# 7474-strobe-generator-v2.net
KiCad netlist of a schematic drawn in EAGLE
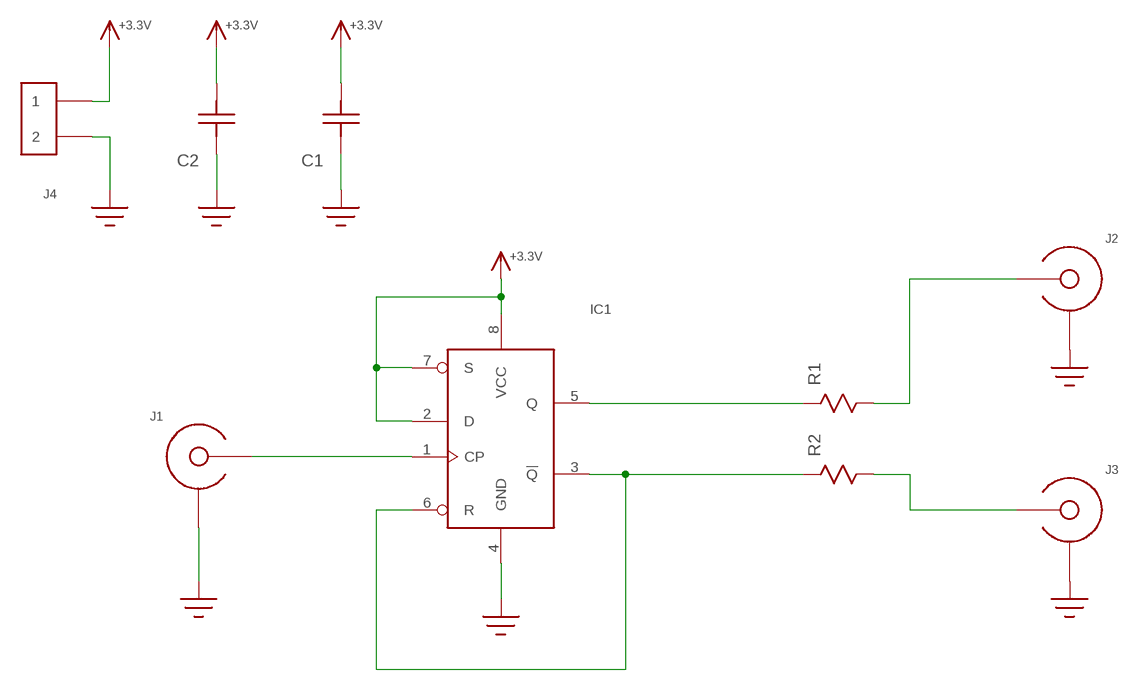
[diagram p0: schematic, sheet 1]

(export (version "E")
  (design (tool "Eeschema 10.0.6"))
  (components
    (comp (ref "C1")
      (value "C0603")
      (footprint "eagle-import:C0603")
      (libsource (lib "eagle-import") (part "C0603"))
    )
    (comp (ref "C2")
      (value "C1206")
      (footprint "eagle-import:1206")
      (libsource (lib "eagle-import") (part "C1206"))
    )
    (comp (ref "IC1")
      (value "74LVC2G74")
      (footprint "eagle-import:SSOP8")
      (libsource (lib "eagle-import") (part "74LVC2G74"))
    )
    (comp (ref "J1")
      (value "SMA-EDGE-LAUNCH4020_TAPER")
      (footprint "eagle-import:SMA_EDGE_LAUNCH_2L_4020_TAPER")
      (libsource (lib "eagle-import") (part "SMA-EDGE-LAUNCH4020_TAPER"))
    )
    (comp (ref "J2")
      (value "SMA-EDGE-LAUNCH4020_TAPER")
      (footprint "eagle-import:SMA_EDGE_LAUNCH_2L_4020_TAPER")
      (libsource (lib "eagle-import") (part "SMA-EDGE-LAUNCH4020_TAPER"))
    )
    (comp (ref "J3")
      (value "SMA-EDGE-LAUNCH4020_TAPER")
      (footprint "eagle-import:SMA_EDGE_LAUNCH_2L_4020_TAPER")
      (libsource (lib "eagle-import") (part "SMA-EDGE-LAUNCH4020_TAPER"))
    )
    (comp (ref "J4")
      (value "HEADER_2PIN")
      (footprint "eagle-import:HEADER_2PIN")
      (libsource (lib "eagle-import") (part "HEADER_2PIN"))
    )
    (comp (ref "R1")
      (value "R0603")
      (footprint "eagle-import:R0603")
      (libsource (lib "eagle-import") (part "R0603"))
    )
    (comp (ref "R2")
      (value "R0603")
      (footprint "eagle-import:R0603")
      (libsource (lib "eagle-import") (part "R0603"))
    )
  )
  (nets
    (net (code "1") (name "+3.3V") (class "Default")
      (node (ref "C1") (pin "P$1") (pinfunction "P$1_P$1") (pintype "bidirectional"))
      (node (ref "C2") (pin "P$1") (pinfunction "P$1_P$1") (pintype "bidirectional"))
      (node (ref "IC1") (pin "2") (pinfunction "D_2") (pintype "bidirectional"))
      (node (ref "IC1") (pin "7") (pinfunction "S_7") (pintype "bidirectional"))
      (node (ref "IC1") (pin "8") (pinfunction "VCC_8") (pintype "bidirectional"))
      (node (ref "J4") (pin "1") (pinfunction "1_1") (pintype "bidirectional"))
    )
    (net (code "2") (name "GND") (class "Default")
      (node (ref "C1") (pin "P$2") (pinfunction "P$2_P$2") (pintype "bidirectional"))
      (node (ref "C2") (pin "P$2") (pinfunction "P$2_P$2") (pintype "bidirectional"))
      (node (ref "IC1") (pin "4") (pinfunction "GND_4") (pintype "bidirectional"))
      (node (ref "J1") (pin "BOTTOM_GND") (pinfunction "SHIELD_BOTTOM_GND") (pintype "bidirectional"))
      (node (ref "J1") (pin "GND@1") (pinfunction "SHIELD_GND@1") (pintype "bidirectional"))
      (node (ref "J1") (pin "GND@14") (pinfunction "SHIELD_GND@14") (pintype "bidirectional"))
      (node (ref "J1") (pin "GND@15") (pinfunction "SHIELD_GND@15") (pintype "bidirectional"))
      (node (ref "J1") (pin "GND@16") (pinfunction "SHIELD_GND@16") (pintype "bidirectional"))
      (node (ref "J1") (pin "GND@17") (pinfunction "SHIELD_GND@17") (pintype "bidirectional"))
      (node (ref "J1") (pin "GND@2") (pinfunction "SHIELD_GND@2") (pintype "bidirectional"))
      (node (ref "J1") (pin "GND@3") (pinfunction "SHIELD_GND@3") (pintype "bidirectional"))
      (node (ref "J1") (pin "GND@4") (pinfunction "SHIELD_GND@4") (pintype "bidirectional"))
      (node (ref "J1") (pin "GND@5") (pinfunction "SHIELD_GND@5") (pintype "bidirectional"))
      (node (ref "J1") (pin "GND@6") (pinfunction "SHIELD_GND@6") (pintype "bidirectional"))
      (node (ref "J1") (pin "GND@7") (pinfunction "SHIELD_GND@7") (pintype "bidirectional"))
      (node (ref "J1") (pin "GND@8") (pinfunction "SHIELD_GND@8") (pintype "bidirectional"))
      (node (ref "J1") (pin "GND_PAD1") (pinfunction "SHIELD_GND_PAD1") (pintype "bidirectional"))
      (node (ref "J1") (pin "GND_PAD2") (pinfunction "SHIELD_GND_PAD2") (pintype "bidirectional"))
      (node (ref "J1") (pin "P$1") (pinfunction "SHIELD_P$1") (pintype "bidirectional"))
      (node (ref "J1") (pin "P$2") (pinfunction "SHIELD_P$2") (pintype "bidirectional"))
      (node (ref "J2") (pin "BOTTOM_GND") (pinfunction "SHIELD_BOTTOM_GND") (pintype "bidirectional"))
      (node (ref "J2") (pin "GND@1") (pinfunction "SHIELD_GND@1") (pintype "bidirectional"))
      (node (ref "J2") (pin "GND@14") (pinfunction "SHIELD_GND@14") (pintype "bidirectional"))
      (node (ref "J2") (pin "GND@15") (pinfunction "SHIELD_GND@15") (pintype "bidirectional"))
      (node (ref "J2") (pin "GND@16") (pinfunction "SHIELD_GND@16") (pintype "bidirectional"))
      (node (ref "J2") (pin "GND@17") (pinfunction "SHIELD_GND@17") (pintype "bidirectional"))
      (node (ref "J2") (pin "GND@2") (pinfunction "SHIELD_GND@2") (pintype "bidirectional"))
      (node (ref "J2") (pin "GND@3") (pinfunction "SHIELD_GND@3") (pintype "bidirectional"))
      (node (ref "J2") (pin "GND@4") (pinfunction "SHIELD_GND@4") (pintype "bidirectional"))
      (node (ref "J2") (pin "GND@5") (pinfunction "SHIELD_GND@5") (pintype "bidirectional"))
      (node (ref "J2") (pin "GND@6") (pinfunction "SHIELD_GND@6") (pintype "bidirectional"))
      (node (ref "J2") (pin "GND@7") (pinfunction "SHIELD_GND@7") (pintype "bidirectional"))
      (node (ref "J2") (pin "GND@8") (pinfunction "SHIELD_GND@8") (pintype "bidirectional"))
      (node (ref "J2") (pin "GND_PAD1") (pinfunction "SHIELD_GND_PAD1") (pintype "bidirectional"))
      (node (ref "J2") (pin "GND_PAD2") (pinfunction "SHIELD_GND_PAD2") (pintype "bidirectional"))
      (node (ref "J2") (pin "P$1") (pinfunction "SHIELD_P$1") (pintype "bidirectional"))
      (node (ref "J2") (pin "P$2") (pinfunction "SHIELD_P$2") (pintype "bidirectional"))
      (node (ref "J3") (pin "BOTTOM_GND") (pinfunction "SHIELD_BOTTOM_GND") (pintype "bidirectional"))
      (node (ref "J3") (pin "GND@1") (pinfunction "SHIELD_GND@1") (pintype "bidirectional"))
      (node (ref "J3") (pin "GND@14") (pinfunction "SHIELD_GND@14") (pintype "bidirectional"))
      (node (ref "J3") (pin "GND@15") (pinfunction "SHIELD_GND@15") (pintype "bidirectional"))
      (node (ref "J3") (pin "GND@16") (pinfunction "SHIELD_GND@16") (pintype "bidirectional"))
      (node (ref "J3") (pin "GND@17") (pinfunction "SHIELD_GND@17") (pintype "bidirectional"))
      (node (ref "J3") (pin "GND@2") (pinfunction "SHIELD_GND@2") (pintype "bidirectional"))
      (node (ref "J3") (pin "GND@3") (pinfunction "SHIELD_GND@3") (pintype "bidirectional"))
      (node (ref "J3") (pin "GND@4") (pinfunction "SHIELD_GND@4") (pintype "bidirectional"))
      (node (ref "J3") (pin "GND@5") (pinfunction "SHIELD_GND@5") (pintype "bidirectional"))
      (node (ref "J3") (pin "GND@6") (pinfunction "SHIELD_GND@6") (pintype "bidirectional"))
      (node (ref "J3") (pin "GND@7") (pinfunction "SHIELD_GND@7") (pintype "bidirectional"))
      (node (ref "J3") (pin "GND@8") (pinfunction "SHIELD_GND@8") (pintype "bidirectional"))
      (node (ref "J3") (pin "GND_PAD1") (pinfunction "SHIELD_GND_PAD1") (pintype "bidirectional"))
      (node (ref "J3") (pin "GND_PAD2") (pinfunction "SHIELD_GND_PAD2") (pintype "bidirectional"))
      (node (ref "J3") (pin "P$1") (pinfunction "SHIELD_P$1") (pintype "bidirectional"))
      (node (ref "J3") (pin "P$2") (pinfunction "SHIELD_P$2") (pintype "bidirectional"))
      (node (ref "J4") (pin "2") (pinfunction "2_2") (pintype "bidirectional"))
    )
    (net (code "3") (name "Net-(IC1-CP)") (class "Default")
      (node (ref "IC1") (pin "1") (pinfunction "CP_1") (pintype "bidirectional"))
      (node (ref "J1") (pin "CENTER@1") (pinfunction "CENTER_CENTER@1") (pintype "bidirectional"))
    )
    (net (code "4") (name "Net-(IC1-Q)") (class "Default")
      (node (ref "IC1") (pin "5") (pinfunction "Q_5") (pintype "bidirectional"))
      (node (ref "R1") (pin "P$1") (pinfunction "P$3_P$1") (pintype "bidirectional"))
    )
    (net (code "5") (name "Net-(IC1-R)") (class "Default")
      (node (ref "IC1") (pin "3") (pinfunction "~{Q}_3") (pintype "bidirectional"))
      (node (ref "IC1") (pin "6") (pinfunction "R_6") (pintype "bidirectional"))
      (node (ref "R2") (pin "P$1") (pinfunction "P$3_P$1") (pintype "bidirectional"))
    )
    (net (code "6") (name "Net-(J2-CENTER)") (class "Default")
      (node (ref "J2") (pin "CENTER@1") (pinfunction "CENTER_CENTER@1") (pintype "bidirectional"))
      (node (ref "R1") (pin "P$2") (pinfunction "P$4_P$2") (pintype "bidirectional"))
    )
    (net (code "7") (name "Net-(J3-CENTER)") (class "Default")
      (node (ref "J3") (pin "CENTER@1") (pinfunction "CENTER_CENTER@1") (pintype "bidirectional"))
      (node (ref "R2") (pin "P$2") (pinfunction "P$4_P$2") (pintype "bidirectional"))
    )
  )
)
